# -modifi.net
KiCad netlist of a schematic drawn in Altium Designer
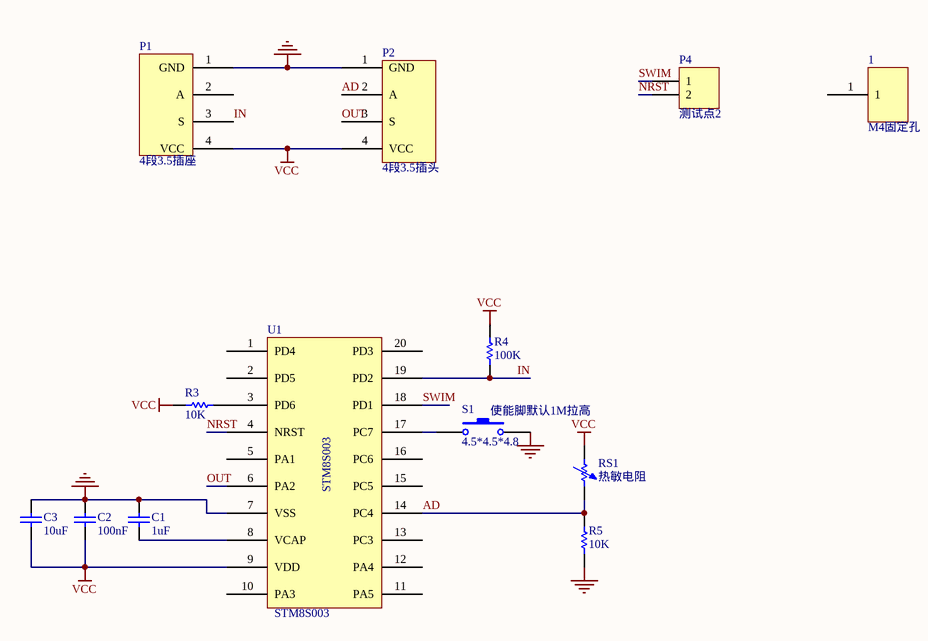
[diagram p0: 热敏开关-modifi.SchDoc]

(export (version "E")
  (design (tool "Eeschema 10.0.6"))
  (components
    (comp (ref "1") (value "M4固定孔") (footprint "M4固定孔") (libsource (lib "DDL6.30") (part "M4固定孔")))
    (comp (ref "C1")
      (value "1uF")
      (footprint "0603C")
      (description "Capacitor")
      (fields (field (name "PUBLISHER") "Altium Limited"))
      (libsource (lib "Miscellaneous Devices") (part "Cap"))
    )
    (comp (ref "C2")
      (value "100nF")
      (footprint "0603C")
      (description "Capacitor")
      (fields (field (name "PUBLISHER") "Altium Limited"))
      (libsource (lib "Miscellaneous Devices") (part "Cap"))
    )
    (comp (ref "C3")
      (value "10uF")
      (footprint "0603C")
      (description "Capacitor")
      (fields (field (name "PUBLISHER") "Altium Limited"))
      (libsource (lib "Miscellaneous Devices") (part "Cap"))
    )
    (comp (ref "P1") (value "4段3.5插座") (footprint "4段3.5耳机贴片座") (libsource (lib "DDL6.30") (part "4段3.5插座")))
    (comp (ref "P2") (value "4段3.5插头") (footprint "4段3.5插头") (libsource (lib "DDL6.30") (part "4段3.5插头")))
    (comp (ref "P4")
      (value "测试点2")
      (footprint "2SMT-2.54")
      (description "Header, 2-Pin")
      (fields (field (name "PUBLISHER") "Altium Limited"))
      (libsource (lib "Miscellaneous Connectors") (part "Header 2"))
    )
    (comp (ref "R3")
      (value "10K")
      (footprint "0603R")
      (description "Resistor")
      (fields (field (name "PUBLISHER") "Altium Limited"))
      (libsource (lib "Miscellaneous Devices") (part "Res1"))
    )
    (comp (ref "R4")
      (value "100K")
      (footprint "0603R")
      (description "Resistor")
      (fields (field (name "PUBLISHER") "Altium Limited"))
      (libsource (lib "Miscellaneous Devices") (part "Res1"))
    )
    (comp (ref "R5")
      (value "10K")
      (footprint "0603R")
      (description "Resistor")
      (fields (field (name "PUBLISHER") "Altium Limited"))
      (libsource (lib "Miscellaneous Devices") (part "Res1"))
    )
    (comp (ref "RS1")
      (value "热敏电阻")
      (footprint "PH2.0-2P")
      (description "Variable Resistor")
      (fields (field (name "PUBLISHER") "Altium Limited"))
      (libsource (lib "Miscellaneous Devices") (part "Res Adj1"))
    )
    (comp (ref "S1")
      (value "4.5*4.5*4.8")
      (footprint "按键4.5*4.5*4.8")
      (description "Switch")
      (fields (field (name "PUBLISHER") "Altium Limited"))
      (libsource (lib "Miscellaneous Devices") (part "SW-PB"))
    )
    (comp (ref "U1") (value "STM8S003") (footprint "TSSOP20") (libsource (lib "DDL6.30") (part "STM8S003")))
  )
  (nets
    (net (code "1") (name "/AD") (class "Default")
      (node (ref "P2") (pin "2") (pinfunction "A_2") (pintype "passive"))
      (node (ref "R5") (pin "2") (pinfunction "2_2") (pintype "passive"))
      (node (ref "RS1") (pin "2") (pinfunction "2_2") (pintype "passive"))
      (node (ref "U1") (pin "14") (pinfunction "PC4_14") (pintype "passive"))
    )
    (net (code "2") (name "/IN") (class "Default")
      (node (ref "P1") (pin "3") (pinfunction "S_3") (pintype "passive"))
      (node (ref "R4") (pin "2") (pinfunction "2_2") (pintype "passive"))
      (node (ref "U1") (pin "19") (pinfunction "PD2_19") (pintype "passive"))
    )
    (net (code "3") (name "/NRST") (class "Default")
      (node (ref "P4") (pin "2") (pinfunction "2_2") (pintype "passive"))
      (node (ref "U1") (pin "4") (pinfunction "NRST_4") (pintype "passive"))
    )
    (net (code "4") (name "/OUT") (class "Default")
      (node (ref "P2") (pin "3") (pinfunction "S_3") (pintype "passive"))
      (node (ref "U1") (pin "6") (pinfunction "PA2_6") (pintype "passive"))
    )
    (net (code "5") (name "/SWIM") (class "Default")
      (node (ref "P4") (pin "1") (pinfunction "1_1") (pintype "passive"))
      (node (ref "U1") (pin "18") (pinfunction "PD1_18") (pintype "passive"))
    )
    (net (code "6") (name "GND") (class "Default")
      (node (ref "C1") (pin "2") (pinfunction "2_2") (pintype "passive"))
      (node (ref "C2") (pin "2") (pinfunction "2_2") (pintype "passive"))
      (node (ref "C3") (pin "2") (pinfunction "2_2") (pintype "passive"))
      (node (ref "P1") (pin "1") (pinfunction "GND_1") (pintype "passive"))
      (node (ref "P2") (pin "1") (pinfunction "GND_1") (pintype "passive"))
      (node (ref "R5") (pin "1") (pinfunction "1_1") (pintype "passive"))
      (node (ref "S1") (pin "2") (pinfunction "2_2") (pintype "passive"))
      (node (ref "U1") (pin "7") (pinfunction "VSS_7") (pintype "passive"))
    )
    (net (code "7") (name "Net-(U1-PC7)") (class "Default")
      (node (ref "S1") (pin "1") (pinfunction "1_1") (pintype "passive"))
      (node (ref "U1") (pin "17") (pinfunction "PC7_17") (pintype "passive"))
    )
    (net (code "8") (name "Net-(U1-PD6)") (class "Default")
      (node (ref "R3") (pin "1") (pinfunction "1_1") (pintype "passive"))
      (node (ref "U1") (pin "3") (pinfunction "PD6_3") (pintype "passive"))
    )
    (net (code "9") (name "Net-(U1-VCAP)") (class "Default")
      (node (ref "C1") (pin "1") (pinfunction "1_1") (pintype "passive"))
      (node (ref "U1") (pin "8") (pinfunction "VCAP_8") (pintype "passive"))
    )
    (net (code "10") (name "VCC") (class "Default")
      (node (ref "C2") (pin "1") (pinfunction "1_1") (pintype "passive"))
      (node (ref "C3") (pin "1") (pinfunction "1_1") (pintype "passive"))
      (node (ref "P1") (pin "4") (pinfunction "VCC_4") (pintype "passive"))
      (node (ref "P2") (pin "4") (pinfunction "VCC_4") (pintype "passive"))
      (node (ref "R3") (pin "2") (pinfunction "2_2") (pintype "passive"))
      (node (ref "R4") (pin "1") (pinfunction "1_1") (pintype "passive"))
      (node (ref "RS1") (pin "1") (pinfunction "1_1") (pintype "passive"))
      (node (ref "U1") (pin "9") (pinfunction "VDD_9") (pintype "passive"))
    )
    (net (code "11") (name "unconnected-(1-Pad1)") (class "Default")
      (node (ref "1") (pin "1") (pinfunction "1_1") (pintype "passive"))
    )
    (net (code "12") (name "unconnected-(P1-A-Pad2)") (class "Default")
      (node (ref "P1") (pin "2") (pinfunction "A_2") (pintype "passive"))
    )
    (net (code "13") (name "unconnected-(U1-PA1-Pad5)") (class "Default")
      (node (ref "U1") (pin "5") (pinfunction "PA1_5") (pintype "passive"))
    )
    (net (code "14") (name "unconnected-(U1-PA3-Pad10)") (class "Default")
      (node (ref "U1") (pin "10") (pinfunction "PA3_10") (pintype "passive"))
    )
    (net (code "15") (name "unconnected-(U1-PA4-Pad12)") (class "Default")
      (node (ref "U1") (pin "12") (pinfunction "PA4_12") (pintype "passive"))
    )
    (net (code "16") (name "unconnected-(U1-PA5-Pad11)") (class "Default")
      (node (ref "U1") (pin "11") (pinfunction "PA5_11") (pintype "passive"))
    )
    (net (code "17") (name "unconnected-(U1-PC3-Pad13)") (class "Default")
      (node (ref "U1") (pin "13") (pinfunction "PC3_13") (pintype "passive"))
    )
    (net (code "18") (name "unconnected-(U1-PC5-Pad15)") (class "Default")
      (node (ref "U1") (pin "15") (pinfunction "PC5_15") (pintype "passive"))
    )
    (net (code "19") (name "unconnected-(U1-PC6-Pad16)") (class "Default")
      (node (ref "U1") (pin "16") (pinfunction "PC6_16") (pintype "passive"))
    )
    (net (code "20") (name "unconnected-(U1-PD3-Pad20)") (class "Default")
      (node (ref "U1") (pin "20") (pinfunction "PD3_20") (pintype "passive"))
    )
    (net (code "21") (name "unconnected-(U1-PD4-Pad1)") (class "Default")
      (node (ref "U1") (pin "1") (pinfunction "PD4_1") (pintype "passive"))
    )
    (net (code "22") (name "unconnected-(U1-PD5-Pad2)") (class "Default")
      (node (ref "U1") (pin "2") (pinfunction "PD5_2") (pintype "passive"))
    )
  )
)
